# sensorstation_ok4.net
KiCad netlist of a schematic drawn in EAGLE
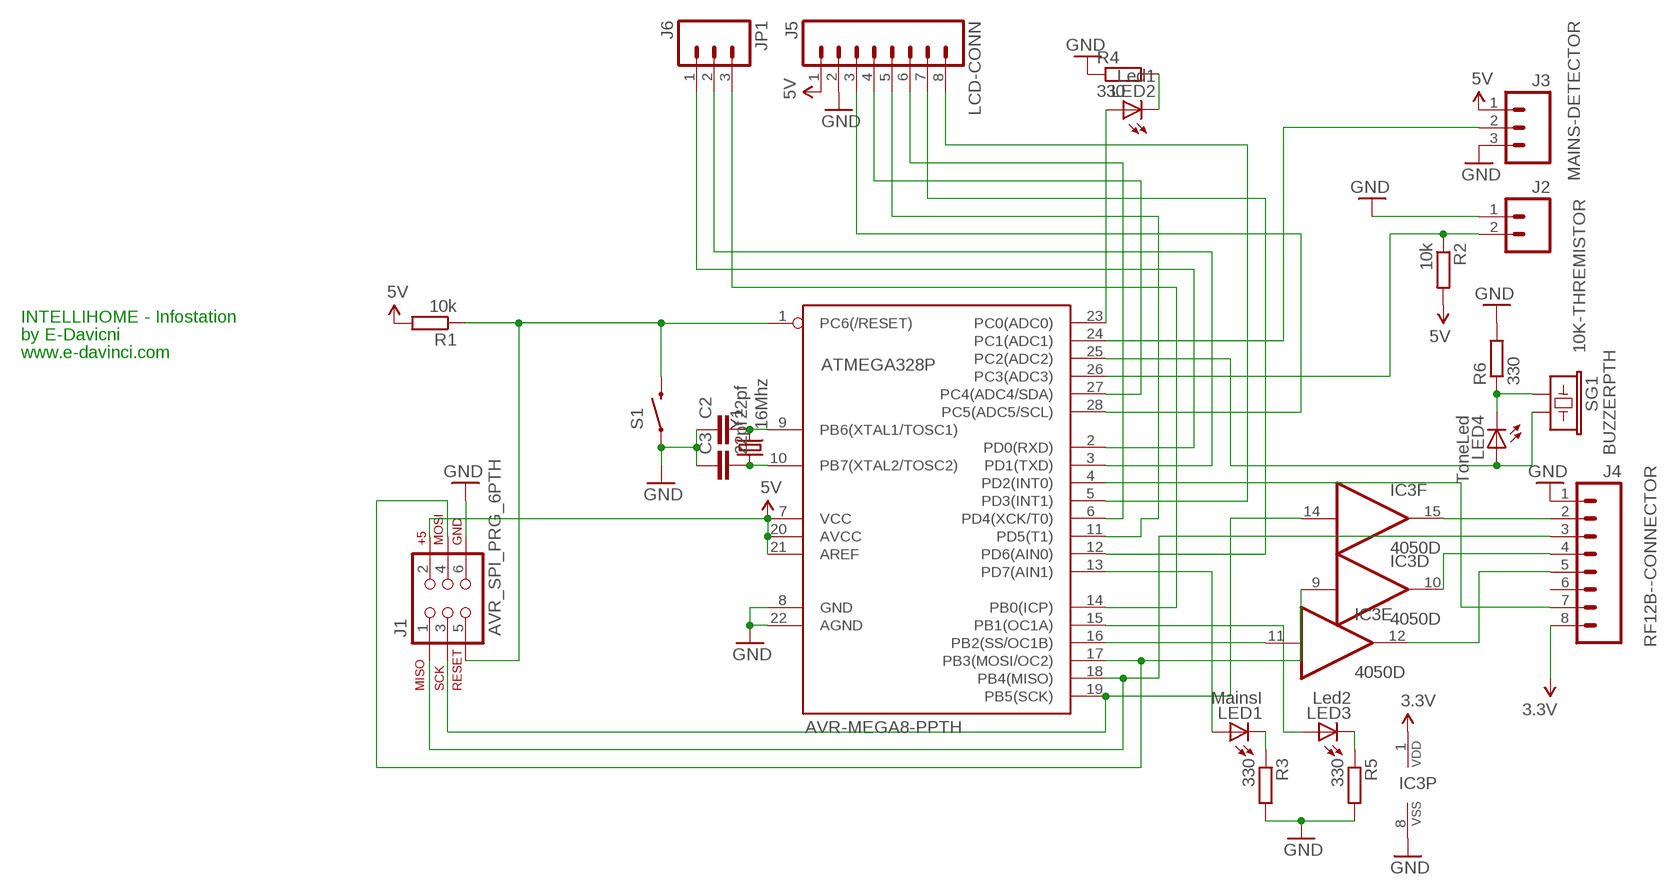
[diagram p0: schematic, sheet 1]

(export (version "E")
  (design (tool "Eeschema 10.0.6"))
  (components
    (comp (ref "10K-THREMISTOR")
      (value "J2")
      (footprint "eagle-import:1X02")
      (libsource (lib "eagle-import") (part "M02PTH"))
    )
    (comp (ref "ATMEGA328P")
      (value "AVR-MEGA8-PPTH")
      (footprint "eagle-import:DIL28-3")
      (libsource (lib "eagle-import") (part "AVR-MEGA8-PPTH"))
    )
    (comp (ref "C2")
      (value "22pf")
      (footprint "eagle-import:CAP-PTH-SMALL")
      (libsource (lib "eagle-import") (part "CAPPTH"))
    )
    (comp (ref "C3")
      (value "22pf")
      (footprint "eagle-import:CAP-PTH-SMALL")
      (libsource (lib "eagle-import") (part "CAPPTH"))
    )
    (comp (ref "IC3")
      (value "4050D")
      (footprint "eagle-import:SO16")
      (libsource (lib "eagle-import") (part "4050D"))
    )
    (comp (ref "J1")
      (value "AVR_SPI_PRG_6PTH")
      (footprint "eagle-import:2X3")
      (libsource (lib "eagle-import") (part "AVR_SPI_PRG_6PTH"))
    )
    (comp (ref "JP1")
      (value "J6")
      (footprint "eagle-import:1X03")
      (libsource (lib "eagle-import") (part "M03PTH"))
    )
    (comp (ref "LCD-CONN")
      (value "J5")
      (footprint "eagle-import:1X08")
      (libsource (lib "eagle-import") (part "M081X08"))
    )
    (comp (ref "LED1")
      (value "MainsI")
      (footprint "eagle-import:LED3MM")
      (libsource (lib "eagle-import") (part "LED3MM"))
    )
    (comp (ref "LED2")
      (value "Led1")
      (footprint "eagle-import:LED3MM")
      (libsource (lib "eagle-import") (part "LED3MM"))
    )
    (comp (ref "LED3")
      (value "Led2")
      (footprint "eagle-import:LED3MM")
      (libsource (lib "eagle-import") (part "LED3MM"))
    )
    (comp (ref "LED4")
      (value "ToneLed")
      (footprint "eagle-import:LED3MM")
      (libsource (lib "eagle-import") (part "LED3MM"))
    )
    (comp (ref "MAINS-DETECTOR")
      (value "J3")
      (footprint "eagle-import:1X03")
      (libsource (lib "eagle-import") (part "M03PTH"))
    )
    (comp (ref "R1")
      (value "10k")
      (footprint "eagle-import:0207_2V")
      (libsource (lib "eagle-import") (part "R-EU_0207/2V"))
    )
    (comp (ref "R2")
      (value "10k")
      (footprint "eagle-import:0207_2V")
      (libsource (lib "eagle-import") (part "R-EU_0207/2V"))
    )
    (comp (ref "R3")
      (value "330")
      (footprint "eagle-import:0207_2V")
      (libsource (lib "eagle-import") (part "R-EU_0207/2V"))
    )
    (comp (ref "R4")
      (value "330")
      (footprint "eagle-import:0207_2V")
      (libsource (lib "eagle-import") (part "R-EU_0207/2V"))
    )
    (comp (ref "R5")
      (value "330")
      (footprint "eagle-import:0207_2V")
      (libsource (lib "eagle-import") (part "R-EU_0207/2V"))
    )
    (comp (ref "R6")
      (value "330")
      (footprint "eagle-import:0207_2V")
      (libsource (lib "eagle-import") (part "R-EU_0207/2V"))
    )
    (comp (ref "RF12B--CONNECTOR")
      (value "J4")
      (footprint "eagle-import:1X08_LONGPADS")
      (libsource (lib "eagle-import") (part "M08LONGPADS"))
    )
    (comp (ref "S1")
      (value "SWITCH-MOMENTARY-2PTH")
      (footprint "eagle-import:TACTILE-PTH")
      (libsource (lib "eagle-import") (part "SWITCH-MOMENTARY-2PTH"))
    )
    (comp (ref "SG1")
      (value "BUZZERPTH")
      (footprint "eagle-import:BUZZER-12MM")
      (libsource (lib "eagle-import") (part "BUZZERPTH"))
    )
    (comp (ref "Y1")
      (value "16Mhz")
      (footprint "eagle-import:HC49US")
      (libsource (lib "eagle-import") (part "CRYSTALHC49US"))
    )
  )
  (nets
    (net (code "1") (name "3.3V") (class "Default")
      (node (ref "IC3") (pin "1") (pinfunction "VDD_1") (pintype "power_in"))
      (node (ref "RF12B--CONNECTOR") (pin "8") (pinfunction "8_8") (pintype "passive"))
    )
    (net (code "2") (name "5V") (class "Default")
      (node (ref "ATMEGA328P") (pin "20") (pinfunction "AVCC_20") (pintype "bidirectional"))
      (node (ref "ATMEGA328P") (pin "21") (pinfunction "AREF_21") (pintype "bidirectional"))
      (node (ref "ATMEGA328P") (pin "7") (pinfunction "VCC_7") (pintype "bidirectional"))
      (node (ref "J1") (pin "2") (pinfunction "2_2") (pintype "passive"))
      (node (ref "LCD-CONN") (pin "1") (pinfunction "1_1") (pintype "passive"))
      (node (ref "MAINS-DETECTOR") (pin "1") (pinfunction "1_1") (pintype "passive"))
      (node (ref "R1") (pin "2") (pinfunction "2_2") (pintype "passive"))
      (node (ref "R2") (pin "2") (pinfunction "2_2") (pintype "passive"))
    )
    (net (code "3") (name "GND") (class "Default")
      (node (ref "10K-THREMISTOR") (pin "1") (pinfunction "1_1") (pintype "passive"))
      (node (ref "ATMEGA328P") (pin "22") (pinfunction "AGND_22") (pintype "bidirectional"))
      (node (ref "ATMEGA328P") (pin "8") (pinfunction "GND_8") (pintype "bidirectional"))
      (node (ref "C2") (pin "1") (pinfunction "1_1") (pintype "passive"))
      (node (ref "C3") (pin "1") (pinfunction "1_1") (pintype "passive"))
      (node (ref "IC3") (pin "8") (pinfunction "VSS_8") (pintype "power_in"))
      (node (ref "J1") (pin "6") (pinfunction "6_6") (pintype "passive"))
      (node (ref "LCD-CONN") (pin "2") (pinfunction "2_2") (pintype "passive"))
      (node (ref "MAINS-DETECTOR") (pin "3") (pinfunction "3_3") (pintype "passive"))
      (node (ref "R3") (pin "2") (pinfunction "2_2") (pintype "passive"))
      (node (ref "R4") (pin "1") (pinfunction "1_1") (pintype "passive"))
      (node (ref "R5") (pin "2") (pinfunction "2_2") (pintype "passive"))
      (node (ref "R6") (pin "2") (pinfunction "2_2") (pintype "passive"))
      (node (ref "RF12B--CONNECTOR") (pin "1") (pinfunction "1_1") (pintype "passive"))
      (node (ref "S1") (pin "1") (pinfunction "1_1") (pintype "passive"))
    )
    (net (code "4") (name "Net-(ATMEGA328P-PB0(ICP))") (class "Default")
      (node (ref "ATMEGA328P") (pin "14") (pinfunction "PB0(ICP)_14") (pintype "bidirectional"))
      (node (ref "JP1") (pin "3") (pinfunction "3_3") (pintype "passive"))
    )
    (net (code "5") (name "Net-(ATMEGA328P-PB1(OC1A))") (class "Default")
      (node (ref "ATMEGA328P") (pin "15") (pinfunction "PB1(OC1A)_15") (pintype "bidirectional"))
      (node (ref "LED3") (pin "A") (pinfunction "A_A") (pintype "passive"))
    )
    (net (code "6") (name "Net-(ATMEGA328P-PB2(SS{slash}OC1B))") (class "Default")
      (node (ref "ATMEGA328P") (pin "16") (pinfunction "PB2(SS/OC1B)_16") (pintype "bidirectional"))
      (node (ref "IC3") (pin "11") (pinfunction "I_11") (pintype "input"))
    )
    (net (code "7") (name "Net-(ATMEGA328P-PB3(MOSI{slash}OC2))") (class "Default")
      (node (ref "ATMEGA328P") (pin "17") (pinfunction "PB3(MOSI/OC2)_17") (pintype "bidirectional"))
      (node (ref "IC3") (pin "9") (pinfunction "I_9") (pintype "input"))
      (node (ref "J1") (pin "4") (pinfunction "4_4") (pintype "passive"))
    )
    (net (code "8") (name "Net-(ATMEGA328P-PB4(MISO))") (class "Default")
      (node (ref "ATMEGA328P") (pin "18") (pinfunction "PB4(MISO)_18") (pintype "bidirectional"))
      (node (ref "J1") (pin "1") (pinfunction "1_1") (pintype "passive"))
      (node (ref "RF12B--CONNECTOR") (pin "3") (pinfunction "3_3") (pintype "passive"))
    )
    (net (code "9") (name "Net-(ATMEGA328P-PB5(SCK))") (class "Default")
      (node (ref "ATMEGA328P") (pin "19") (pinfunction "PB5(SCK)_19") (pintype "bidirectional"))
      (node (ref "IC3") (pin "14") (pinfunction "I_14") (pintype "input"))
      (node (ref "J1") (pin "3") (pinfunction "3_3") (pintype "passive"))
    )
    (net (code "10") (name "Net-(ATMEGA328P-PB6(XTAL1{slash}TOSC1))") (class "Default")
      (node (ref "ATMEGA328P") (pin "9") (pinfunction "PB6(XTAL1/TOSC1)_9") (pintype "bidirectional"))
      (node (ref "C2") (pin "2") (pinfunction "2_2") (pintype "passive"))
      (node (ref "Y1") (pin "2") (pinfunction "2_2") (pintype "passive"))
    )
    (net (code "11") (name "Net-(ATMEGA328P-PB7(XTAL2{slash}TOSC2))") (class "Default")
      (node (ref "ATMEGA328P") (pin "10") (pinfunction "PB7(XTAL2/TOSC2)_10") (pintype "bidirectional"))
      (node (ref "C3") (pin "2") (pinfunction "2_2") (pintype "passive"))
      (node (ref "Y1") (pin "1") (pinfunction "1_1") (pintype "passive"))
    )
    (net (code "12") (name "Net-(ATMEGA328P-PC0(ADC0))") (class "Default")
      (node (ref "ATMEGA328P") (pin "23") (pinfunction "PC0(ADC0)_23") (pintype "bidirectional"))
      (node (ref "LED2") (pin "A") (pinfunction "A_A") (pintype "passive"))
    )
    (net (code "13") (name "Net-(ATMEGA328P-PC1(ADC1))") (class "Default")
      (node (ref "ATMEGA328P") (pin "24") (pinfunction "PC1(ADC1)_24") (pintype "bidirectional"))
      (node (ref "MAINS-DETECTOR") (pin "2") (pinfunction "2_2") (pintype "passive"))
    )
    (net (code "14") (name "Net-(ATMEGA328P-PC2(ADC2))") (class "Default")
      (node (ref "ATMEGA328P") (pin "25") (pinfunction "PC2(ADC2)_25") (pintype "bidirectional"))
      (node (ref "LED4") (pin "A") (pinfunction "A_A") (pintype "passive"))
      (node (ref "SG1") (pin "-") (pinfunction "2_-") (pintype "passive"))
    )
    (net (code "15") (name "Net-(ATMEGA328P-PC3(ADC3))") (class "Default")
      (node (ref "10K-THREMISTOR") (pin "2") (pinfunction "2_2") (pintype "passive"))
      (node (ref "ATMEGA328P") (pin "26") (pinfunction "PC3(ADC3)_26") (pintype "bidirectional"))
      (node (ref "R2") (pin "1") (pinfunction "1_1") (pintype "passive"))
    )
    (net (code "16") (name "Net-(ATMEGA328P-PC4(ADC4{slash}SDA))") (class "Default")
      (node (ref "ATMEGA328P") (pin "27") (pinfunction "PC4(ADC4/SDA)_27") (pintype "bidirectional"))
      (node (ref "LCD-CONN") (pin "4") (pinfunction "4_4") (pintype "passive"))
    )
    (net (code "17") (name "Net-(ATMEGA328P-PC5(ADC5{slash}SCL))") (class "Default")
      (node (ref "ATMEGA328P") (pin "28") (pinfunction "PC5(ADC5/SCL)_28") (pintype "bidirectional"))
      (node (ref "LCD-CONN") (pin "3") (pinfunction "3_3") (pintype "passive"))
    )
    (net (code "18") (name "Net-(ATMEGA328P-PC6({slash}RESET))") (class "Default")
      (node (ref "ATMEGA328P") (pin "1") (pinfunction "PC6(/RESET)_1") (pintype "bidirectional"))
      (node (ref "J1") (pin "5") (pinfunction "5_5") (pintype "passive"))
      (node (ref "R1") (pin "1") (pinfunction "1_1") (pintype "passive"))
      (node (ref "S1") (pin "3") (pinfunction "2_3") (pintype "passive"))
    )
    (net (code "19") (name "Net-(ATMEGA328P-PD0(RXD))") (class "Default")
      (node (ref "ATMEGA328P") (pin "2") (pinfunction "PD0(RXD)_2") (pintype "bidirectional"))
      (node (ref "JP1") (pin "1") (pinfunction "1_1") (pintype "passive"))
    )
    (net (code "20") (name "Net-(ATMEGA328P-PD1(TXD))") (class "Default")
      (node (ref "ATMEGA328P") (pin "3") (pinfunction "PD1(TXD)_3") (pintype "bidirectional"))
      (node (ref "JP1") (pin "2") (pinfunction "2_2") (pintype "passive"))
    )
    (net (code "21") (name "Net-(ATMEGA328P-PD2(INT0))") (class "Default")
      (node (ref "ATMEGA328P") (pin "4") (pinfunction "PD2(INT0)_4") (pintype "bidirectional"))
      (node (ref "RF12B--CONNECTOR") (pin "7") (pinfunction "7_7") (pintype "passive"))
    )
    (net (code "22") (name "Net-(ATMEGA328P-PD3(INT1))") (class "Default")
      (node (ref "ATMEGA328P") (pin "5") (pinfunction "PD3(INT1)_5") (pintype "bidirectional"))
      (node (ref "LCD-CONN") (pin "8") (pinfunction "8_8") (pintype "passive"))
    )
    (net (code "23") (name "Net-(ATMEGA328P-PD4(XCK{slash}T0))") (class "Default")
      (node (ref "ATMEGA328P") (pin "6") (pinfunction "PD4(XCK/T0)_6") (pintype "bidirectional"))
      (node (ref "LCD-CONN") (pin "6") (pinfunction "6_6") (pintype "passive"))
    )
    (net (code "24") (name "Net-(ATMEGA328P-PD5(T1))") (class "Default")
      (node (ref "ATMEGA328P") (pin "11") (pinfunction "PD5(T1)_11") (pintype "bidirectional"))
      (node (ref "LCD-CONN") (pin "5") (pinfunction "5_5") (pintype "passive"))
    )
    (net (code "25") (name "Net-(ATMEGA328P-PD6(AIN0))") (class "Default")
      (node (ref "ATMEGA328P") (pin "12") (pinfunction "PD6(AIN0)_12") (pintype "bidirectional"))
      (node (ref "LCD-CONN") (pin "7") (pinfunction "7_7") (pintype "passive"))
    )
    (net (code "26") (name "Net-(ATMEGA328P-PD7(AIN1))") (class "Default")
      (node (ref "ATMEGA328P") (pin "13") (pinfunction "PD7(AIN1)_13") (pintype "bidirectional"))
      (node (ref "LED1") (pin "A") (pinfunction "A_A") (pintype "passive"))
    )
    (net (code "27") (name "Net-(IC3D-O)") (class "Default")
      (node (ref "IC3") (pin "10") (pinfunction "O_10") (pintype "output"))
      (node (ref "RF12B--CONNECTOR") (pin "4") (pinfunction "4_4") (pintype "passive"))
    )
    (net (code "28") (name "Net-(IC3E-O)") (class "Default")
      (node (ref "IC3") (pin "12") (pinfunction "O_12") (pintype "output"))
      (node (ref "RF12B--CONNECTOR") (pin "5") (pinfunction "5_5") (pintype "passive"))
    )
    (net (code "29") (name "Net-(IC3F-O)") (class "Default")
      (node (ref "IC3") (pin "15") (pinfunction "O_15") (pintype "output"))
      (node (ref "RF12B--CONNECTOR") (pin "2") (pinfunction "2_2") (pintype "passive"))
    )
    (net (code "30") (name "Net-(LED1-C)") (class "Default")
      (node (ref "LED1") (pin "K") (pinfunction "C_K") (pintype "passive"))
      (node (ref "R3") (pin "1") (pinfunction "1_1") (pintype "passive"))
    )
    (net (code "31") (name "Net-(LED2-C)") (class "Default")
      (node (ref "LED2") (pin "K") (pinfunction "C_K") (pintype "passive"))
      (node (ref "R4") (pin "2") (pinfunction "2_2") (pintype "passive"))
    )
    (net (code "32") (name "Net-(LED3-C)") (class "Default")
      (node (ref "LED3") (pin "K") (pinfunction "C_K") (pintype "passive"))
      (node (ref "R5") (pin "1") (pinfunction "1_1") (pintype "passive"))
    )
    (net (code "33") (name "Net-(LED4-C)") (class "Default")
      (node (ref "LED4") (pin "K") (pinfunction "C_K") (pintype "passive"))
      (node (ref "R6") (pin "1") (pinfunction "1_1") (pintype "passive"))
      (node (ref "SG1") (pin "+") (pinfunction "1_+") (pintype "passive"))
    )
    (net (code "34") (name "unconnected-(RF12B--CONNECTOR-Pad6)") (class "Default")
      (node (ref "RF12B--CONNECTOR") (pin "6") (pinfunction "6_6") (pintype "passive"))
    )
  )
)
